# sb-sonata-fpgapwr2.net
KiCad netlist of a schematic drawn in Altium Designer
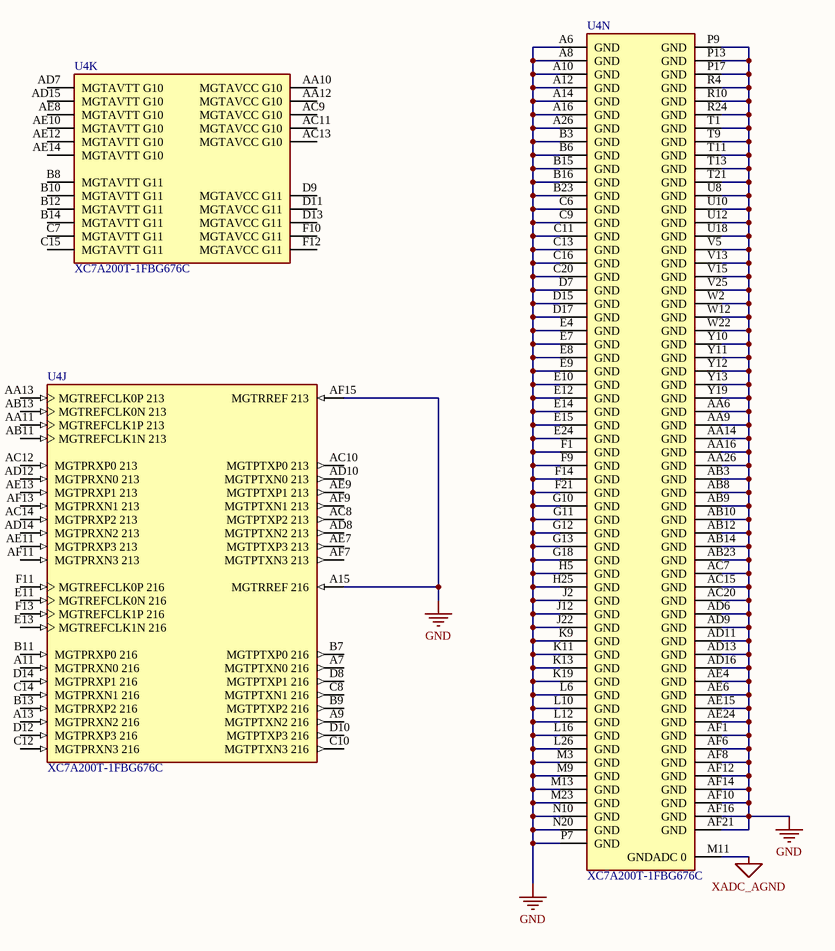
[diagram p0: sb-sonata-fpgapwr2.SchDoc]

(export (version "E")
  (design (tool "Eeschema 10.0.6"))
  (components
    (comp (ref "U4")
      (value "XC7A200T-1FBG676C")
      (footprint "FP-XC7A200T-1FBG676C-MFG")
      (description "IC FPGA 400 I/O 676FCBGA")
      (fields
        (field (name "OCTOPART") "https://octopart.com/xc7a200t-1fbg676c-xilinx-27810760")
        (field (name "MANUFACTURER") "Xilinx")
      )
      (libsource (lib "Altium Content Vault") (part "4b217bf1b8a92a9e4e40d14dbdee1ba"))
    )
  )
  (nets
    (net (code "1") (name "GND") (class "Default")
      (node (ref "U4") (pin "A10") (pinfunction "GND_A10") (pintype "power_in"))
      (node (ref "U4") (pin "A12") (pinfunction "GND_A12") (pintype "power_in"))
      (node (ref "U4") (pin "A14") (pinfunction "GND_A14") (pintype "power_in"))
      (node (ref "U4") (pin "A15") (pinfunction "MGTRREF_216_A15") (pintype "input"))
      (node (ref "U4") (pin "A16") (pinfunction "GND_A16") (pintype "power_in"))
      (node (ref "U4") (pin "A26") (pinfunction "GND_A26") (pintype "power_in"))
      (node (ref "U4") (pin "A6") (pinfunction "GND_A6") (pintype "power_in"))
      (node (ref "U4") (pin "A8") (pinfunction "GND_A8") (pintype "power_in"))
      (node (ref "U4") (pin "AA14") (pinfunction "GND_AA14") (pintype "power_in"))
      (node (ref "U4") (pin "AA16") (pinfunction "GND_AA16") (pintype "power_in"))
      (node (ref "U4") (pin "AA26") (pinfunction "GND_AA26") (pintype "power_in"))
      (node (ref "U4") (pin "AA6") (pinfunction "GND_AA6") (pintype "power_in"))
      (node (ref "U4") (pin "AA9") (pinfunction "GND_AA9") (pintype "power_in"))
      (node (ref "U4") (pin "AB10") (pinfunction "GND_AB10") (pintype "power_in"))
      (node (ref "U4") (pin "AB12") (pinfunction "GND_AB12") (pintype "power_in"))
      (node (ref "U4") (pin "AB14") (pinfunction "GND_AB14") (pintype "power_in"))
      (node (ref "U4") (pin "AB23") (pinfunction "GND_AB23") (pintype "power_in"))
      (node (ref "U4") (pin "AB3") (pinfunction "GND_AB3") (pintype "power_in"))
      (node (ref "U4") (pin "AB8") (pinfunction "GND_AB8") (pintype "power_in"))
      (node (ref "U4") (pin "AB9") (pinfunction "GND_AB9") (pintype "power_in"))
      (node (ref "U4") (pin "AC15") (pinfunction "GND_AC15") (pintype "power_in"))
      (node (ref "U4") (pin "AC20") (pinfunction "GND_AC20") (pintype "power_in"))
      (node (ref "U4") (pin "AC7") (pinfunction "GND_AC7") (pintype "power_in"))
      (node (ref "U4") (pin "AD11") (pinfunction "GND_AD11") (pintype "power_in"))
      (node (ref "U4") (pin "AD13") (pinfunction "GND_AD13") (pintype "power_in"))
      (node (ref "U4") (pin "AD16") (pinfunction "GND_AD16") (pintype "power_in"))
      (node (ref "U4") (pin "AD6") (pinfunction "GND_AD6") (pintype "power_in"))
      (node (ref "U4") (pin "AD9") (pinfunction "GND_AD9") (pintype "power_in"))
      (node (ref "U4") (pin "AE15") (pinfunction "GND_AE15") (pintype "power_in"))
      (node (ref "U4") (pin "AE24") (pinfunction "GND_AE24") (pintype "power_in"))
      (node (ref "U4") (pin "AE4") (pinfunction "GND_AE4") (pintype "power_in"))
      (node (ref "U4") (pin "AE6") (pinfunction "GND_AE6") (pintype "power_in"))
      (node (ref "U4") (pin "AF1") (pinfunction "GND_AF1") (pintype "power_in"))
      (node (ref "U4") (pin "AF10") (pinfunction "GND_AF10") (pintype "power_in"))
      (node (ref "U4") (pin "AF12") (pinfunction "GND_AF12") (pintype "power_in"))
      (node (ref "U4") (pin "AF14") (pinfunction "GND_AF14") (pintype "power_in"))
      (node (ref "U4") (pin "AF15") (pinfunction "MGTRREF_213_AF15") (pintype "input"))
      (node (ref "U4") (pin "AF16") (pinfunction "GND_AF16") (pintype "power_in"))
      (node (ref "U4") (pin "AF21") (pinfunction "GND_AF21") (pintype "power_in"))
      (node (ref "U4") (pin "AF6") (pinfunction "GND_AF6") (pintype "power_in"))
      (node (ref "U4") (pin "AF8") (pinfunction "GND_AF8") (pintype "power_in"))
      (node (ref "U4") (pin "B15") (pinfunction "GND_B15") (pintype "power_in"))
      (node (ref "U4") (pin "B16") (pinfunction "GND_B16") (pintype "power_in"))
      (node (ref "U4") (pin "B23") (pinfunction "GND_B23") (pintype "power_in"))
      (node (ref "U4") (pin "B3") (pinfunction "GND_B3") (pintype "power_in"))
      (node (ref "U4") (pin "B6") (pinfunction "GND_B6") (pintype "power_in"))
      (node (ref "U4") (pin "C11") (pinfunction "GND_C11") (pintype "power_in"))
      (node (ref "U4") (pin "C13") (pinfunction "GND_C13") (pintype "power_in"))
      (node (ref "U4") (pin "C16") (pinfunction "GND_C16") (pintype "power_in"))
      (node (ref "U4") (pin "C20") (pinfunction "GND_C20") (pintype "power_in"))
      (node (ref "U4") (pin "C6") (pinfunction "GND_C6") (pintype "power_in"))
      (node (ref "U4") (pin "C9") (pinfunction "GND_C9") (pintype "power_in"))
      (node (ref "U4") (pin "D15") (pinfunction "GND_D15") (pintype "power_in"))
      (node (ref "U4") (pin "D17") (pinfunction "GND_D17") (pintype "power_in"))
      (node (ref "U4") (pin "D7") (pinfunction "GND_D7") (pintype "power_in"))
      (node (ref "U4") (pin "E10") (pinfunction "GND_E10") (pintype "power_in"))
      (node (ref "U4") (pin "E12") (pinfunction "GND_E12") (pintype "power_in"))
      (node (ref "U4") (pin "E14") (pinfunction "GND_E14") (pintype "power_in"))
      (node (ref "U4") (pin "E15") (pinfunction "GND_E15") (pintype "power_in"))
      (node (ref "U4") (pin "E24") (pinfunction "GND_E24") (pintype "power_in"))
      (node (ref "U4") (pin "E4") (pinfunction "GND_E4") (pintype "power_in"))
      (node (ref "U4") (pin "E7") (pinfunction "GND_E7") (pintype "power_in"))
      (node (ref "U4") (pin "E8") (pinfunction "GND_E8") (pintype "power_in"))
      (node (ref "U4") (pin "E9") (pinfunction "GND_E9") (pintype "power_in"))
      (node (ref "U4") (pin "F1") (pinfunction "GND_F1") (pintype "power_in"))
      (node (ref "U4") (pin "F14") (pinfunction "GND_F14") (pintype "power_in"))
      (node (ref "U4") (pin "F21") (pinfunction "GND_F21") (pintype "power_in"))
      (node (ref "U4") (pin "F9") (pinfunction "GND_F9") (pintype "power_in"))
      (node (ref "U4") (pin "G10") (pinfunction "GND_G10") (pintype "power_in"))
      (node (ref "U4") (pin "G11") (pinfunction "GND_G11") (pintype "power_in"))
      (node (ref "U4") (pin "G12") (pinfunction "GND_G12") (pintype "power_in"))
      (node (ref "U4") (pin "G13") (pinfunction "GND_G13") (pintype "power_in"))
      (node (ref "U4") (pin "G18") (pinfunction "GND_G18") (pintype "power_in"))
      (node (ref "U4") (pin "H25") (pinfunction "GND_H25") (pintype "power_in"))
      (node (ref "U4") (pin "H5") (pinfunction "GND_H5") (pintype "power_in"))
      (node (ref "U4") (pin "J12") (pinfunction "GND_J12") (pintype "power_in"))
      (node (ref "U4") (pin "J2") (pinfunction "GND_J2") (pintype "power_in"))
      (node (ref "U4") (pin "J22") (pinfunction "GND_J22") (pintype "power_in"))
      (node (ref "U4") (pin "K11") (pinfunction "GND_K11") (pintype "power_in"))
      (node (ref "U4") (pin "K13") (pinfunction "GND_K13") (pintype "power_in"))
      (node (ref "U4") (pin "K19") (pinfunction "GND_K19") (pintype "power_in"))
      (node (ref "U4") (pin "K9") (pinfunction "GND_K9") (pintype "power_in"))
      (node (ref "U4") (pin "L10") (pinfunction "GND_L10") (pintype "power_in"))
      (node (ref "U4") (pin "L12") (pinfunction "GND_L12") (pintype "power_in"))
      (node (ref "U4") (pin "L16") (pinfunction "GND_L16") (pintype "power_in"))
      (node (ref "U4") (pin "L26") (pinfunction "GND_L26") (pintype "power_in"))
      (node (ref "U4") (pin "L6") (pinfunction "GND_L6") (pintype "power_in"))
      (node (ref "U4") (pin "M13") (pinfunction "GND_M13") (pintype "power_in"))
      (node (ref "U4") (pin "M23") (pinfunction "GND_M23") (pintype "power_in"))
      (node (ref "U4") (pin "M3") (pinfunction "GND_M3") (pintype "power_in"))
      (node (ref "U4") (pin "M9") (pinfunction "GND_M9") (pintype "power_in"))
      (node (ref "U4") (pin "N10") (pinfunction "GND_N10") (pintype "power_in"))
      (node (ref "U4") (pin "N20") (pinfunction "GND_N20") (pintype "power_in"))
      (node (ref "U4") (pin "P13") (pinfunction "GND_P13") (pintype "power_in"))
      (node (ref "U4") (pin "P17") (pinfunction "GND_P17") (pintype "power_in"))
      (node (ref "U4") (pin "P7") (pinfunction "GND_P7") (pintype "power_in"))
      (node (ref "U4") (pin "P9") (pinfunction "GND_P9") (pintype "power_in"))
      (node (ref "U4") (pin "R10") (pinfunction "GND_R10") (pintype "power_in"))
      (node (ref "U4") (pin "R24") (pinfunction "GND_R24") (pintype "power_in"))
      (node (ref "U4") (pin "R4") (pinfunction "GND_R4") (pintype "power_in"))
      (node (ref "U4") (pin "T1") (pinfunction "GND_T1") (pintype "power_in"))
      (node (ref "U4") (pin "T11") (pinfunction "GND_T11") (pintype "power_in"))
      (node (ref "U4") (pin "T13") (pinfunction "GND_T13") (pintype "power_in"))
      (node (ref "U4") (pin "T21") (pinfunction "GND_T21") (pintype "power_in"))
      (node (ref "U4") (pin "T9") (pinfunction "GND_T9") (pintype "power_in"))
      (node (ref "U4") (pin "U10") (pinfunction "GND_U10") (pintype "power_in"))
      (node (ref "U4") (pin "U12") (pinfunction "GND_U12") (pintype "power_in"))
      (node (ref "U4") (pin "U18") (pinfunction "GND_U18") (pintype "power_in"))
      (node (ref "U4") (pin "U8") (pinfunction "GND_U8") (pintype "power_in"))
      (node (ref "U4") (pin "V13") (pinfunction "GND_V13") (pintype "power_in"))
      (node (ref "U4") (pin "V15") (pinfunction "GND_V15") (pintype "power_in"))
      (node (ref "U4") (pin "V25") (pinfunction "GND_V25") (pintype "power_in"))
      (node (ref "U4") (pin "V5") (pinfunction "GND_V5") (pintype "power_in"))
      (node (ref "U4") (pin "W12") (pinfunction "GND_W12") (pintype "power_in"))
      (node (ref "U4") (pin "W2") (pinfunction "GND_W2") (pintype "power_in"))
      (node (ref "U4") (pin "W22") (pinfunction "GND_W22") (pintype "power_in"))
      (node (ref "U4") (pin "Y10") (pinfunction "GND_Y10") (pintype "power_in"))
      (node (ref "U4") (pin "Y11") (pinfunction "GND_Y11") (pintype "power_in"))
      (node (ref "U4") (pin "Y12") (pinfunction "GND_Y12") (pintype "power_in"))
      (node (ref "U4") (pin "Y13") (pinfunction "GND_Y13") (pintype "power_in"))
      (node (ref "U4") (pin "Y19") (pinfunction "GND_Y19") (pintype "power_in"))
    )
    (net (code "2") (name "XADC_AGND") (class "Default")
      (node (ref "U4") (pin "M11") (pinfunction "GNDADC_0_M11") (pintype "power_in"))
    )
    (net (code "3") (name "unconnected-(U4J-MGTPRXN0_213-PadAD12)") (class "Default")
      (node (ref "U4") (pin "AD12") (pinfunction "MGTPRXN0_213_AD12") (pintype "input"))
    )
    (net (code "4") (name "unconnected-(U4J-MGTPRXN0_216-PadA11)") (class "Default")
      (node (ref "U4") (pin "A11") (pinfunction "MGTPRXN0_216_A11") (pintype "input"))
    )
    (net (code "5") (name "unconnected-(U4J-MGTPRXN1_213-PadAF13)") (class "Default")
      (node (ref "U4") (pin "AF13") (pinfunction "MGTPRXN1_213_AF13") (pintype "input"))
    )
    (net (code "6") (name "unconnected-(U4J-MGTPRXN1_216-PadC14)") (class "Default")
      (node (ref "U4") (pin "C14") (pinfunction "MGTPRXN1_216_C14") (pintype "input"))
    )
    (net (code "7") (name "unconnected-(U4J-MGTPRXN2_213-PadAD14)") (class "Default")
      (node (ref "U4") (pin "AD14") (pinfunction "MGTPRXN2_213_AD14") (pintype "input"))
    )
    (net (code "8") (name "unconnected-(U4J-MGTPRXN2_216-PadA13)") (class "Default")
      (node (ref "U4") (pin "A13") (pinfunction "MGTPRXN2_216_A13") (pintype "input"))
    )
    (net (code "9") (name "unconnected-(U4J-MGTPRXN3_213-PadAF11)") (class "Default")
      (node (ref "U4") (pin "AF11") (pinfunction "MGTPRXN3_213_AF11") (pintype "input"))
    )
    (net (code "10") (name "unconnected-(U4J-MGTPRXN3_216-PadC12)") (class "Default")
      (node (ref "U4") (pin "C12") (pinfunction "MGTPRXN3_216_C12") (pintype "input"))
    )
    (net (code "11") (name "unconnected-(U4J-MGTPRXP0_213-PadAC12)") (class "Default")
      (node (ref "U4") (pin "AC12") (pinfunction "MGTPRXP0_213_AC12") (pintype "input"))
    )
    (net (code "12") (name "unconnected-(U4J-MGTPRXP0_216-PadB11)") (class "Default")
      (node (ref "U4") (pin "B11") (pinfunction "MGTPRXP0_216_B11") (pintype "input"))
    )
    (net (code "13") (name "unconnected-(U4J-MGTPRXP1_213-PadAE13)") (class "Default")
      (node (ref "U4") (pin "AE13") (pinfunction "MGTPRXP1_213_AE13") (pintype "input"))
    )
    (net (code "14") (name "unconnected-(U4J-MGTPRXP1_216-PadD14)") (class "Default")
      (node (ref "U4") (pin "D14") (pinfunction "MGTPRXP1_216_D14") (pintype "input"))
    )
    (net (code "15") (name "unconnected-(U4J-MGTPRXP2_213-PadAC14)") (class "Default")
      (node (ref "U4") (pin "AC14") (pinfunction "MGTPRXP2_213_AC14") (pintype "input"))
    )
    (net (code "16") (name "unconnected-(U4J-MGTPRXP2_216-PadB13)") (class "Default")
      (node (ref "U4") (pin "B13") (pinfunction "MGTPRXP2_216_B13") (pintype "input"))
    )
    (net (code "17") (name "unconnected-(U4J-MGTPRXP3_213-PadAE11)") (class "Default")
      (node (ref "U4") (pin "AE11") (pinfunction "MGTPRXP3_213_AE11") (pintype "input"))
    )
    (net (code "18") (name "unconnected-(U4J-MGTPRXP3_216-PadD12)") (class "Default")
      (node (ref "U4") (pin "D12") (pinfunction "MGTPRXP3_216_D12") (pintype "input"))
    )
    (net (code "19") (name "unconnected-(U4J-MGTPTXN0_213-PadAD10)") (class "Default")
      (node (ref "U4") (pin "AD10") (pinfunction "MGTPTXN0_213_AD10") (pintype "output"))
    )
    (net (code "20") (name "unconnected-(U4J-MGTPTXN0_216-PadA7)") (class "Default")
      (node (ref "U4") (pin "A7") (pinfunction "MGTPTXN0_216_A7") (pintype "output"))
    )
    (net (code "21") (name "unconnected-(U4J-MGTPTXN1_213-PadAF9)") (class "Default")
      (node (ref "U4") (pin "AF9") (pinfunction "MGTPTXN1_213_AF9") (pintype "output"))
    )
    (net (code "22") (name "unconnected-(U4J-MGTPTXN1_216-PadC8)") (class "Default")
      (node (ref "U4") (pin "C8") (pinfunction "MGTPTXN1_216_C8") (pintype "output"))
    )
    (net (code "23") (name "unconnected-(U4J-MGTPTXN2_213-PadAD8)") (class "Default")
      (node (ref "U4") (pin "AD8") (pinfunction "MGTPTXN2_213_AD8") (pintype "output"))
    )
    (net (code "24") (name "unconnected-(U4J-MGTPTXN2_216-PadA9)") (class "Default")
      (node (ref "U4") (pin "A9") (pinfunction "MGTPTXN2_216_A9") (pintype "output"))
    )
    (net (code "25") (name "unconnected-(U4J-MGTPTXN3_213-PadAF7)") (class "Default")
      (node (ref "U4") (pin "AF7") (pinfunction "MGTPTXN3_213_AF7") (pintype "output"))
    )
    (net (code "26") (name "unconnected-(U4J-MGTPTXN3_216-PadC10)") (class "Default")
      (node (ref "U4") (pin "C10") (pinfunction "MGTPTXN3_216_C10") (pintype "output"))
    )
    (net (code "27") (name "unconnected-(U4J-MGTPTXP0_213-PadAC10)") (class "Default")
      (node (ref "U4") (pin "AC10") (pinfunction "MGTPTXP0_213_AC10") (pintype "output"))
    )
    (net (code "28") (name "unconnected-(U4J-MGTPTXP0_216-PadB7)") (class "Default")
      (node (ref "U4") (pin "B7") (pinfunction "MGTPTXP0_216_B7") (pintype "output"))
    )
    (net (code "29") (name "unconnected-(U4J-MGTPTXP1_213-PadAE9)") (class "Default")
      (node (ref "U4") (pin "AE9") (pinfunction "MGTPTXP1_213_AE9") (pintype "output"))
    )
    (net (code "30") (name "unconnected-(U4J-MGTPTXP1_216-PadD8)") (class "Default")
      (node (ref "U4") (pin "D8") (pinfunction "MGTPTXP1_216_D8") (pintype "output"))
    )
    (net (code "31") (name "unconnected-(U4J-MGTPTXP2_213-PadAC8)") (class "Default")
      (node (ref "U4") (pin "AC8") (pinfunction "MGTPTXP2_213_AC8") (pintype "output"))
    )
    (net (code "32") (name "unconnected-(U4J-MGTPTXP2_216-PadB9)") (class "Default")
      (node (ref "U4") (pin "B9") (pinfunction "MGTPTXP2_216_B9") (pintype "output"))
    )
    (net (code "33") (name "unconnected-(U4J-MGTPTXP3_213-PadAE7)") (class "Default")
      (node (ref "U4") (pin "AE7") (pinfunction "MGTPTXP3_213_AE7") (pintype "output"))
    )
    (net (code "34") (name "unconnected-(U4J-MGTPTXP3_216-PadD10)") (class "Default")
      (node (ref "U4") (pin "D10") (pinfunction "MGTPTXP3_216_D10") (pintype "output"))
    )
    (net (code "35") (name "unconnected-(U4J-MGTREFCLK0N_213-PadAB13)") (class "Default")
      (node (ref "U4") (pin "AB13") (pinfunction "MGTREFCLK0N_213_AB13") (pintype "input"))
    )
    (net (code "36") (name "unconnected-(U4J-MGTREFCLK0N_216-PadE11)") (class "Default")
      (node (ref "U4") (pin "E11") (pinfunction "MGTREFCLK0N_216_E11") (pintype "input"))
    )
    (net (code "37") (name "unconnected-(U4J-MGTREFCLK0P_213-PadAA13)") (class "Default")
      (node (ref "U4") (pin "AA13") (pinfunction "MGTREFCLK0P_213_AA13") (pintype "input"))
    )
    (net (code "38") (name "unconnected-(U4J-MGTREFCLK0P_216-PadF11)") (class "Default")
      (node (ref "U4") (pin "F11") (pinfunction "MGTREFCLK0P_216_F11") (pintype "input"))
    )
    (net (code "39") (name "unconnected-(U4J-MGTREFCLK1N_213-PadAB11)") (class "Default")
      (node (ref "U4") (pin "AB11") (pinfunction "MGTREFCLK1N_213_AB11") (pintype "input"))
    )
    (net (code "40") (name "unconnected-(U4J-MGTREFCLK1N_216-PadE13)") (class "Default")
      (node (ref "U4") (pin "E13") (pinfunction "MGTREFCLK1N_216_E13") (pintype "input"))
    )
    (net (code "41") (name "unconnected-(U4J-MGTREFCLK1P_213-PadAA11)") (class "Default")
      (node (ref "U4") (pin "AA11") (pinfunction "MGTREFCLK1P_213_AA11") (pintype "input"))
    )
    (net (code "42") (name "unconnected-(U4J-MGTREFCLK1P_216-PadF13)") (class "Default")
      (node (ref "U4") (pin "F13") (pinfunction "MGTREFCLK1P_216_F13") (pintype "input"))
    )
    (net (code "43") (name "unconnected-(U4K-MGTAVCC_G10-PadAA10)") (class "Default")
      (node (ref "U4") (pin "AA10") (pinfunction "MGTAVCC_G10_AA10") (pintype "power_in"))
    )
    (net (code "44") (name "unconnected-(U4K-MGTAVCC_G10-PadAA12)") (class "Default")
      (node (ref "U4") (pin "AA12") (pinfunction "MGTAVCC_G10_AA12") (pintype "power_in"))
    )
    (net (code "45") (name "unconnected-(U4K-MGTAVCC_G10-PadAC9)") (class "Default")
      (node (ref "U4") (pin "AC9") (pinfunction "MGTAVCC_G10_AC9") (pintype "power_in"))
    )
    (net (code "46") (name "unconnected-(U4K-MGTAVCC_G10-PadAC11)") (class "Default")
      (node (ref "U4") (pin "AC11") (pinfunction "MGTAVCC_G10_AC11") (pintype "power_in"))
    )
    (net (code "47") (name "unconnected-(U4K-MGTAVCC_G10-PadAC13)") (class "Default")
      (node (ref "U4") (pin "AC13") (pinfunction "MGTAVCC_G10_AC13") (pintype "power_in"))
    )
    (net (code "48") (name "unconnected-(U4K-MGTAVCC_G11-PadD9)") (class "Default")
      (node (ref "U4") (pin "D9") (pinfunction "MGTAVCC_G11_D9") (pintype "power_in"))
    )
    (net (code "49") (name "unconnected-(U4K-MGTAVCC_G11-PadD11)") (class "Default")
      (node (ref "U4") (pin "D11") (pinfunction "MGTAVCC_G11_D11") (pintype "power_in"))
    )
    (net (code "50") (name "unconnected-(U4K-MGTAVCC_G11-PadD13)") (class "Default")
      (node (ref "U4") (pin "D13") (pinfunction "MGTAVCC_G11_D13") (pintype "power_in"))
    )
    (net (code "51") (name "unconnected-(U4K-MGTAVCC_G11-PadF10)") (class "Default")
      (node (ref "U4") (pin "F10") (pinfunction "MGTAVCC_G11_F10") (pintype "power_in"))
    )
    (net (code "52") (name "unconnected-(U4K-MGTAVCC_G11-PadF12)") (class "Default")
      (node (ref "U4") (pin "F12") (pinfunction "MGTAVCC_G11_F12") (pintype "power_in"))
    )
    (net (code "53") (name "unconnected-(U4K-MGTAVTT_G10-PadAD7)") (class "Default")
      (node (ref "U4") (pin "AD7") (pinfunction "MGTAVTT_G10_AD7") (pintype "power_in"))
    )
    (net (code "54") (name "unconnected-(U4K-MGTAVTT_G10-PadAD15)") (class "Default")
      (node (ref "U4") (pin "AD15") (pinfunction "MGTAVTT_G10_AD15") (pintype "power_in"))
    )
    (net (code "55") (name "unconnected-(U4K-MGTAVTT_G10-PadAE8)") (class "Default")
      (node (ref "U4") (pin "AE8") (pinfunction "MGTAVTT_G10_AE8") (pintype "power_in"))
    )
    (net (code "56") (name "unconnected-(U4K-MGTAVTT_G10-PadAE10)") (class "Default")
      (node (ref "U4") (pin "AE10") (pinfunction "MGTAVTT_G10_AE10") (pintype "power_in"))
    )
    (net (code "57") (name "unconnected-(U4K-MGTAVTT_G10-PadAE12)") (class "Default")
      (node (ref "U4") (pin "AE12") (pinfunction "MGTAVTT_G10_AE12") (pintype "power_in"))
    )
    (net (code "58") (name "unconnected-(U4K-MGTAVTT_G10-PadAE14)") (class "Default")
      (node (ref "U4") (pin "AE14") (pinfunction "MGTAVTT_G10_AE14") (pintype "power_in"))
    )
    (net (code "59") (name "unconnected-(U4K-MGTAVTT_G11-PadB8)") (class "Default")
      (node (ref "U4") (pin "B8") (pinfunction "MGTAVTT_G11_B8") (pintype "power_in"))
    )
    (net (code "60") (name "unconnected-(U4K-MGTAVTT_G11-PadB10)") (class "Default")
      (node (ref "U4") (pin "B10") (pinfunction "MGTAVTT_G11_B10") (pintype "power_in"))
    )
    (net (code "61") (name "unconnected-(U4K-MGTAVTT_G11-PadB12)") (class "Default")
      (node (ref "U4") (pin "B12") (pinfunction "MGTAVTT_G11_B12") (pintype "power_in"))
    )
    (net (code "62") (name "unconnected-(U4K-MGTAVTT_G11-PadB14)") (class "Default")
      (node (ref "U4") (pin "B14") (pinfunction "MGTAVTT_G11_B14") (pintype "power_in"))
    )
    (net (code "63") (name "unconnected-(U4K-MGTAVTT_G11-PadC7)") (class "Default")
      (node (ref "U4") (pin "C7") (pinfunction "MGTAVTT_G11_C7") (pintype "power_in"))
    )
    (net (code "64") (name "unconnected-(U4K-MGTAVTT_G11-PadC15)") (class "Default")
      (node (ref "U4") (pin "C15") (pinfunction "MGTAVTT_G11_C15") (pintype "power_in"))
    )
  )
)
